# Schematic.net
KiCad netlist of a schematic drawn in EAGLE
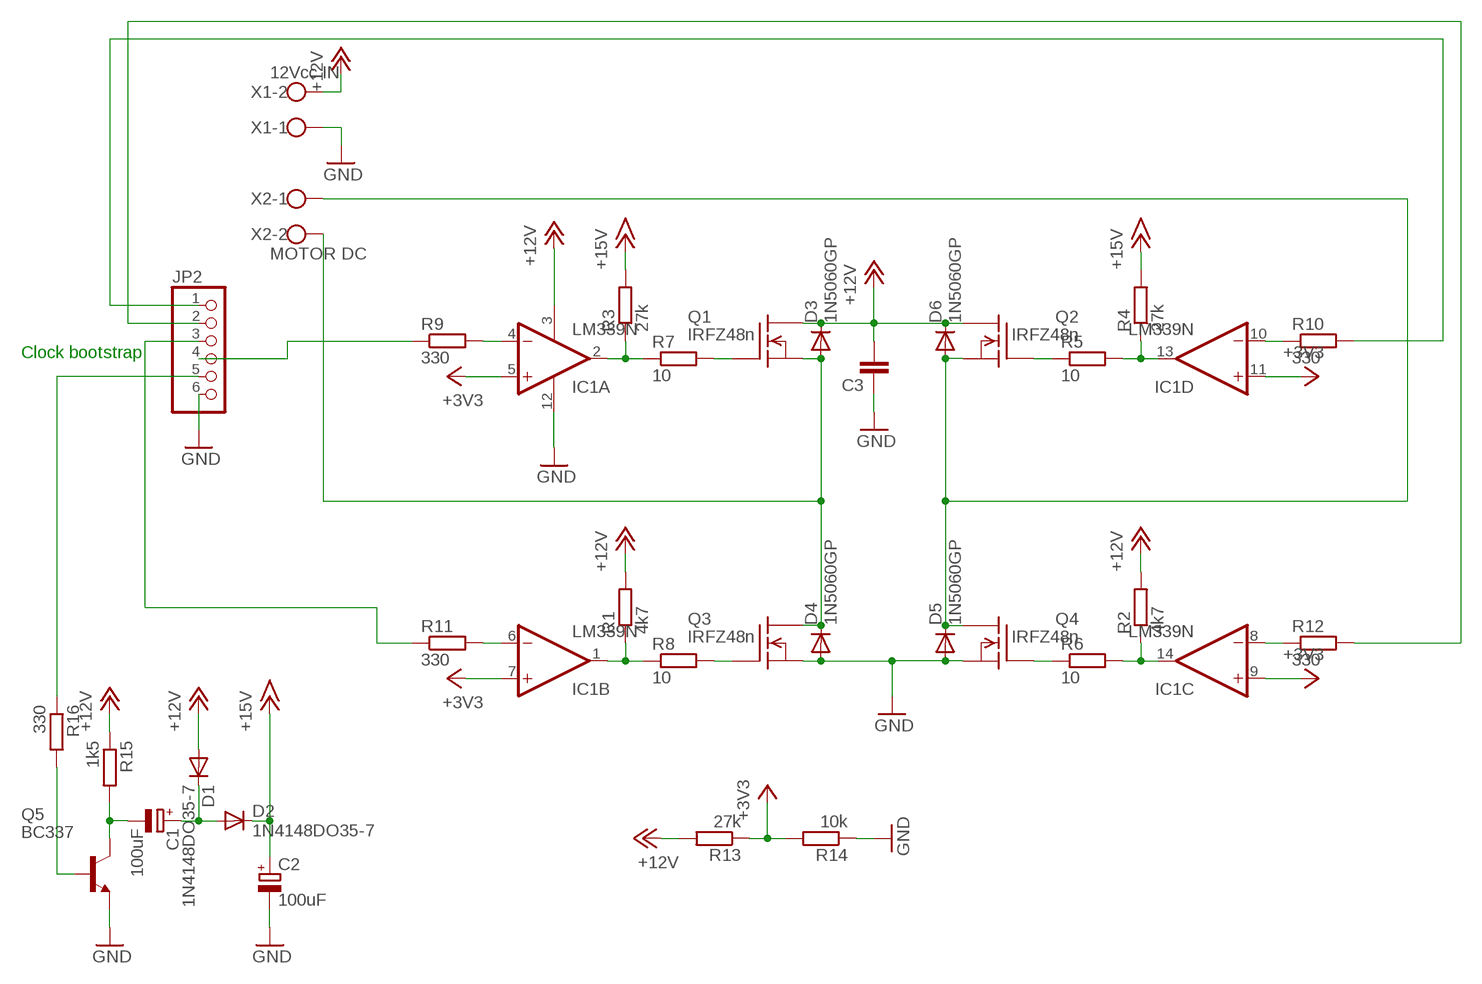
[diagram p0: schematic, sheet 1]

(export (version "E")
  (design (tool "Eeschema 10.0.6"))
  (components
    (comp (ref "C1")
      (value "100uF")
      (footprint "eagle-import:E3,5-8")
      (libsource (lib "eagle-import") (part "CPOL-EUE3.5-8"))
    )
    (comp (ref "C2")
      (value "100uF")
      (footprint "eagle-import:E3,5-8")
      (libsource (lib "eagle-import") (part "CPOL-EUE3.5-8"))
    )
    (comp (ref "C3")
      (value "C-EU050-024X044")
      (footprint "eagle-import:C050-024X044")
      (libsource (lib "eagle-import") (part "C-EU050-024X044"))
    )
    (comp (ref "D1")
      (value "1N4148DO35-7")
      (footprint "eagle-import:DO35-7")
      (libsource (lib "eagle-import") (part "1N4148DO35-7"))
    )
    (comp (ref "D2")
      (value "1N4148DO35-7")
      (footprint "eagle-import:DO35-7")
      (libsource (lib "eagle-import") (part "1N4148DO35-7"))
    )
    (comp (ref "D3")
      (value "1N5060GP")
      (footprint "eagle-import:DO15-12")
      (libsource (lib "eagle-import") (part "1N5060GP"))
    )
    (comp (ref "D4")
      (value "1N5060GP")
      (footprint "eagle-import:DO15-12")
      (libsource (lib "eagle-import") (part "1N5060GP"))
    )
    (comp (ref "D5")
      (value "1N5060GP")
      (footprint "eagle-import:DO15-12")
      (libsource (lib "eagle-import") (part "1N5060GP"))
    )
    (comp (ref "D6")
      (value "1N5060GP")
      (footprint "eagle-import:DO15-12")
      (libsource (lib "eagle-import") (part "1N5060GP"))
    )
    (comp (ref "IC1")
      (value "LM339N")
      (footprint "eagle-import:DIL14")
      (libsource (lib "eagle-import") (part "LM339N"))
    )
    (comp (ref "JP2")
      (value "PINHD-1X6")
      (footprint "eagle-import:1X06")
      (libsource (lib "eagle-import") (part "PINHD-1X6"))
    )
    (comp (ref "Q1")
      (value "IRFZ48n")
      (footprint "eagle-import:TO220")
      (libsource (lib "eagle-import") (part "IRF510"))
    )
    (comp (ref "Q2")
      (value "IRFZ48n")
      (footprint "eagle-import:TO220")
      (libsource (lib "eagle-import") (part "IRF510"))
    )
    (comp (ref "Q3")
      (value "IRFZ48n")
      (footprint "eagle-import:TO220")
      (libsource (lib "eagle-import") (part "IRF510"))
    )
    (comp (ref "Q4")
      (value "IRFZ48n")
      (footprint "eagle-import:TO220")
      (libsource (lib "eagle-import") (part "IRF510"))
    )
    (comp (ref "Q5")
      (value "BC337")
      (footprint "eagle-import:TO92")
      (libsource (lib "eagle-import") (part "BC337"))
    )
    (comp (ref "R1")
      (value "4k7")
      (footprint "eagle-import:0204_7")
      (libsource (lib "eagle-import") (part "R-EU_0204/7"))
    )
    (comp (ref "R2")
      (value "4k7")
      (footprint "eagle-import:0207_10")
      (libsource (lib "eagle-import") (part "R-EU_0207/10"))
    )
    (comp (ref "R3")
      (value "27k")
      (footprint "eagle-import:0204_7")
      (libsource (lib "eagle-import") (part "R-EU_0204/7"))
    )
    (comp (ref "R4")
      (value "27k")
      (footprint "eagle-import:0207_10")
      (libsource (lib "eagle-import") (part "R-EU_0207/10"))
    )
    (comp (ref "R5")
      (value "10")
      (footprint "eagle-import:0207_7")
      (libsource (lib "eagle-import") (part "R-EU_0207/7"))
    )
    (comp (ref "R6")
      (value "10")
      (footprint "eagle-import:0207_10")
      (libsource (lib "eagle-import") (part "R-EU_0207/10"))
    )
    (comp (ref "R7")
      (value "10")
      (footprint "eagle-import:0207_10")
      (libsource (lib "eagle-import") (part "R-EU_0207/10"))
    )
    (comp (ref "R8")
      (value "10")
      (footprint "eagle-import:0207_7")
      (libsource (lib "eagle-import") (part "R-EU_0207/7"))
    )
    (comp (ref "R9")
      (value "330")
      (footprint "eagle-import:0204_7")
      (libsource (lib "eagle-import") (part "R-EU_0204/7"))
    )
    (comp (ref "R10")
      (value "330")
      (footprint "eagle-import:0207_7")
      (libsource (lib "eagle-import") (part "R-EU_0207/7"))
    )
    (comp (ref "R11")
      (value "330")
      (footprint "eagle-import:0204_7")
      (libsource (lib "eagle-import") (part "R-EU_0204/7"))
    )
    (comp (ref "R12")
      (value "330")
      (footprint "eagle-import:0207_7")
      (libsource (lib "eagle-import") (part "R-EU_0207/7"))
    )
    (comp (ref "R13")
      (value "27k")
      (footprint "eagle-import:0204_7")
      (libsource (lib "eagle-import") (part "R-EU_0204/7"))
    )
    (comp (ref "R14")
      (value "10k")
      (footprint "eagle-import:0204_7")
      (libsource (lib "eagle-import") (part "R-EU_0204/7"))
    )
    (comp (ref "R15")
      (value "1k5")
      (footprint "eagle-import:0204_5")
      (libsource (lib "eagle-import") (part "R-EU_0204/5"))
    )
    (comp (ref "R16")
      (value "330")
      (footprint "eagle-import:0207_7")
      (libsource (lib "eagle-import") (part "R-EU_0207/7"))
    )
    (comp (ref "X1")
      (value "12Vcc IN")
      (footprint "eagle-import:W237-102")
      (fields (field (name "MPN") "237-102"))
      (libsource (lib "eagle-import") (part "W237-102"))
    )
    (comp (ref "X2")
      (value "MOTOR DC")
      (footprint "eagle-import:W237-102")
      (fields (field (name "MPN") "237-102"))
      (libsource (lib "eagle-import") (part "W237-102"))
    )
  )
  (nets
    (net (code "1") (name "+3V3") (class "Default")
      (node (ref "IC1") (pin "11") (pinfunction "+IN_11") (pintype "input"))
      (node (ref "IC1") (pin "5") (pinfunction "+IN_5") (pintype "input"))
      (node (ref "IC1") (pin "7") (pinfunction "+IN_7") (pintype "input"))
      (node (ref "IC1") (pin "9") (pinfunction "+IN_9") (pintype "input"))
      (node (ref "R13") (pin "1") (pinfunction "1_1") (pintype "passive"))
      (node (ref "R14") (pin "2") (pinfunction "2_2") (pintype "passive"))
    )
    (net (code "2") (name "+12V") (class "Default")
      (node (ref "C3") (pin "2") (pinfunction "2_2") (pintype "passive"))
      (node (ref "D1") (pin "A") (pinfunction "A_A") (pintype "passive"))
      (node (ref "D3") (pin "C") (pinfunction "C_C") (pintype "passive"))
      (node (ref "D6") (pin "C") (pinfunction "C_C") (pintype "passive"))
      (node (ref "IC1") (pin "3") (pinfunction "V+_3") (pintype "power_in"))
      (node (ref "Q1") (pin "2") (pinfunction "D_2") (pintype "passive"))
      (node (ref "Q2") (pin "2") (pinfunction "D_2") (pintype "passive"))
      (node (ref "R1") (pin "2") (pinfunction "2_2") (pintype "passive"))
      (node (ref "R13") (pin "2") (pinfunction "2_2") (pintype "passive"))
      (node (ref "R15") (pin "1") (pinfunction "1_1") (pintype "passive"))
      (node (ref "R2") (pin "2") (pinfunction "2_2") (pintype "passive"))
      (node (ref "X1") (pin "2") (pinfunction "KL_2") (pintype "passive"))
    )
    (net (code "3") (name "+15V") (class "Default")
      (node (ref "C2") (pin "+") (pinfunction "+_+") (pintype "passive"))
      (node (ref "D2") (pin "C") (pinfunction "C_C") (pintype "passive"))
      (node (ref "R3") (pin "2") (pinfunction "2_2") (pintype "passive"))
      (node (ref "R4") (pin "2") (pinfunction "2_2") (pintype "passive"))
    )
    (net (code "4") (name "GND") (class "Default")
      (node (ref "C2") (pin "-") (pinfunction "-_-") (pintype "passive"))
      (node (ref "C3") (pin "1") (pinfunction "1_1") (pintype "passive"))
      (node (ref "D4") (pin "A") (pinfunction "A_A") (pintype "passive"))
      (node (ref "D5") (pin "A") (pinfunction "A_A") (pintype "passive"))
      (node (ref "IC1") (pin "12") (pinfunction "GND_12") (pintype "power_in"))
      (node (ref "JP2") (pin "6") (pinfunction "6_6") (pintype "passive"))
      (node (ref "Q3") (pin "3") (pinfunction "S_3") (pintype "passive"))
      (node (ref "Q4") (pin "3") (pinfunction "S_3") (pintype "passive"))
      (node (ref "Q5") (pin "1") (pinfunction "E_1") (pintype "passive"))
      (node (ref "R14") (pin "1") (pinfunction "1_1") (pintype "passive"))
      (node (ref "X1") (pin "1") (pinfunction "KL_1") (pintype "passive"))
    )
    (net (code "5") (name "Net-(C1-Pad+)") (class "Default")
      (node (ref "C1") (pin "+") (pinfunction "+_+") (pintype "passive"))
      (node (ref "D1") (pin "C") (pinfunction "C_C") (pintype "passive"))
      (node (ref "D2") (pin "A") (pinfunction "A_A") (pintype "passive"))
    )
    (net (code "6") (name "Net-(IC1A--IN)") (class "Default")
      (node (ref "IC1") (pin "4") (pinfunction "-IN_4") (pintype "input"))
      (node (ref "R9") (pin "2") (pinfunction "2_2") (pintype "passive"))
    )
    (net (code "7") (name "Net-(IC1A-OUT)") (class "Default")
      (node (ref "IC1") (pin "2") (pinfunction "OUT_2") (pintype "open_collector"))
      (node (ref "R3") (pin "1") (pinfunction "1_1") (pintype "passive"))
      (node (ref "R7") (pin "1") (pinfunction "1_1") (pintype "passive"))
    )
    (net (code "8") (name "Net-(IC1B--IN)") (class "Default")
      (node (ref "IC1") (pin "6") (pinfunction "-IN_6") (pintype "input"))
      (node (ref "R11") (pin "2") (pinfunction "2_2") (pintype "passive"))
    )
    (net (code "9") (name "Net-(IC1B-OUT)") (class "Default")
      (node (ref "IC1") (pin "1") (pinfunction "OUT_1") (pintype "open_collector"))
      (node (ref "R1") (pin "1") (pinfunction "1_1") (pintype "passive"))
      (node (ref "R8") (pin "1") (pinfunction "1_1") (pintype "passive"))
    )
    (net (code "10") (name "Net-(IC1C--IN)") (class "Default")
      (node (ref "IC1") (pin "8") (pinfunction "-IN_8") (pintype "input"))
      (node (ref "R12") (pin "1") (pinfunction "1_1") (pintype "passive"))
    )
    (net (code "11") (name "Net-(IC1C-OUT)") (class "Default")
      (node (ref "IC1") (pin "14") (pinfunction "OUT_14") (pintype "open_collector"))
      (node (ref "R2") (pin "1") (pinfunction "1_1") (pintype "passive"))
      (node (ref "R6") (pin "2") (pinfunction "2_2") (pintype "passive"))
    )
    (net (code "12") (name "Net-(IC1D--IN)") (class "Default")
      (node (ref "IC1") (pin "10") (pinfunction "-IN_10") (pintype "input"))
      (node (ref "R10") (pin "1") (pinfunction "1_1") (pintype "passive"))
    )
    (net (code "13") (name "Net-(IC1D-OUT)") (class "Default")
      (node (ref "IC1") (pin "13") (pinfunction "OUT_13") (pintype "open_collector"))
      (node (ref "R4") (pin "1") (pinfunction "1_1") (pintype "passive"))
      (node (ref "R5") (pin "2") (pinfunction "2_2") (pintype "passive"))
    )
    (net (code "14") (name "Net-(JP2-Pad1)") (class "Default")
      (node (ref "JP2") (pin "1") (pinfunction "1_1") (pintype "passive"))
      (node (ref "R10") (pin "2") (pinfunction "2_2") (pintype "passive"))
    )
    (net (code "15") (name "Net-(JP2-Pad2)") (class "Default")
      (node (ref "JP2") (pin "2") (pinfunction "2_2") (pintype "passive"))
      (node (ref "R12") (pin "2") (pinfunction "2_2") (pintype "passive"))
    )
    (net (code "16") (name "Net-(JP2-Pad3)") (class "Default")
      (node (ref "JP2") (pin "3") (pinfunction "3_3") (pintype "passive"))
      (node (ref "R11") (pin "1") (pinfunction "1_1") (pintype "passive"))
    )
    (net (code "17") (name "Net-(JP2-Pad4)") (class "Default")
      (node (ref "JP2") (pin "4") (pinfunction "4_4") (pintype "passive"))
      (node (ref "R9") (pin "1") (pinfunction "1_1") (pintype "passive"))
    )
    (net (code "18") (name "Net-(JP2-Pad5)") (class "Default")
      (node (ref "JP2") (pin "5") (pinfunction "5_5") (pintype "passive"))
      (node (ref "R16") (pin "1") (pinfunction "1_1") (pintype "passive"))
    )
    (net (code "19") (name "Net-(Q1-G)") (class "Default")
      (node (ref "Q1") (pin "1") (pinfunction "G_1") (pintype "passive"))
      (node (ref "R7") (pin "2") (pinfunction "2_2") (pintype "passive"))
    )
    (net (code "20") (name "Net-(Q1-S)") (class "Default")
      (node (ref "D3") (pin "A") (pinfunction "A_A") (pintype "passive"))
      (node (ref "D4") (pin "C") (pinfunction "C_C") (pintype "passive"))
      (node (ref "Q1") (pin "3") (pinfunction "S_3") (pintype "passive"))
      (node (ref "Q3") (pin "2") (pinfunction "D_2") (pintype "passive"))
      (node (ref "X2") (pin "2") (pinfunction "KL_2") (pintype "passive"))
    )
    (net (code "21") (name "Net-(Q2-G)") (class "Default")
      (node (ref "Q2") (pin "1") (pinfunction "G_1") (pintype "passive"))
      (node (ref "R5") (pin "1") (pinfunction "1_1") (pintype "passive"))
    )
    (net (code "22") (name "Net-(Q2-S)") (class "Default")
      (node (ref "D5") (pin "C") (pinfunction "C_C") (pintype "passive"))
      (node (ref "D6") (pin "A") (pinfunction "A_A") (pintype "passive"))
      (node (ref "Q2") (pin "3") (pinfunction "S_3") (pintype "passive"))
      (node (ref "Q4") (pin "2") (pinfunction "D_2") (pintype "passive"))
      (node (ref "X2") (pin "1") (pinfunction "KL_1") (pintype "passive"))
    )
    (net (code "23") (name "Net-(Q3-G)") (class "Default")
      (node (ref "Q3") (pin "1") (pinfunction "G_1") (pintype "passive"))
      (node (ref "R8") (pin "2") (pinfunction "2_2") (pintype "passive"))
    )
    (net (code "24") (name "Net-(Q4-G)") (class "Default")
      (node (ref "Q4") (pin "1") (pinfunction "G_1") (pintype "passive"))
      (node (ref "R6") (pin "1") (pinfunction "1_1") (pintype "passive"))
    )
    (net (code "25") (name "Net-(Q5-B)") (class "Default")
      (node (ref "Q5") (pin "2") (pinfunction "B_2") (pintype "passive"))
      (node (ref "R16") (pin "2") (pinfunction "2_2") (pintype "passive"))
    )
    (net (code "26") (name "Net-(Q5-C)") (class "Default")
      (node (ref "C1") (pin "-") (pinfunction "-_-") (pintype "passive"))
      (node (ref "Q5") (pin "3") (pinfunction "C_3") (pintype "passive"))
      (node (ref "R15") (pin "2") (pinfunction "2_2") (pintype "passive"))
    )
  )
)
